# SCH_OpenOllie_2026-02-20.net
KiCad netlist of a schematic drawn in EasyEDA
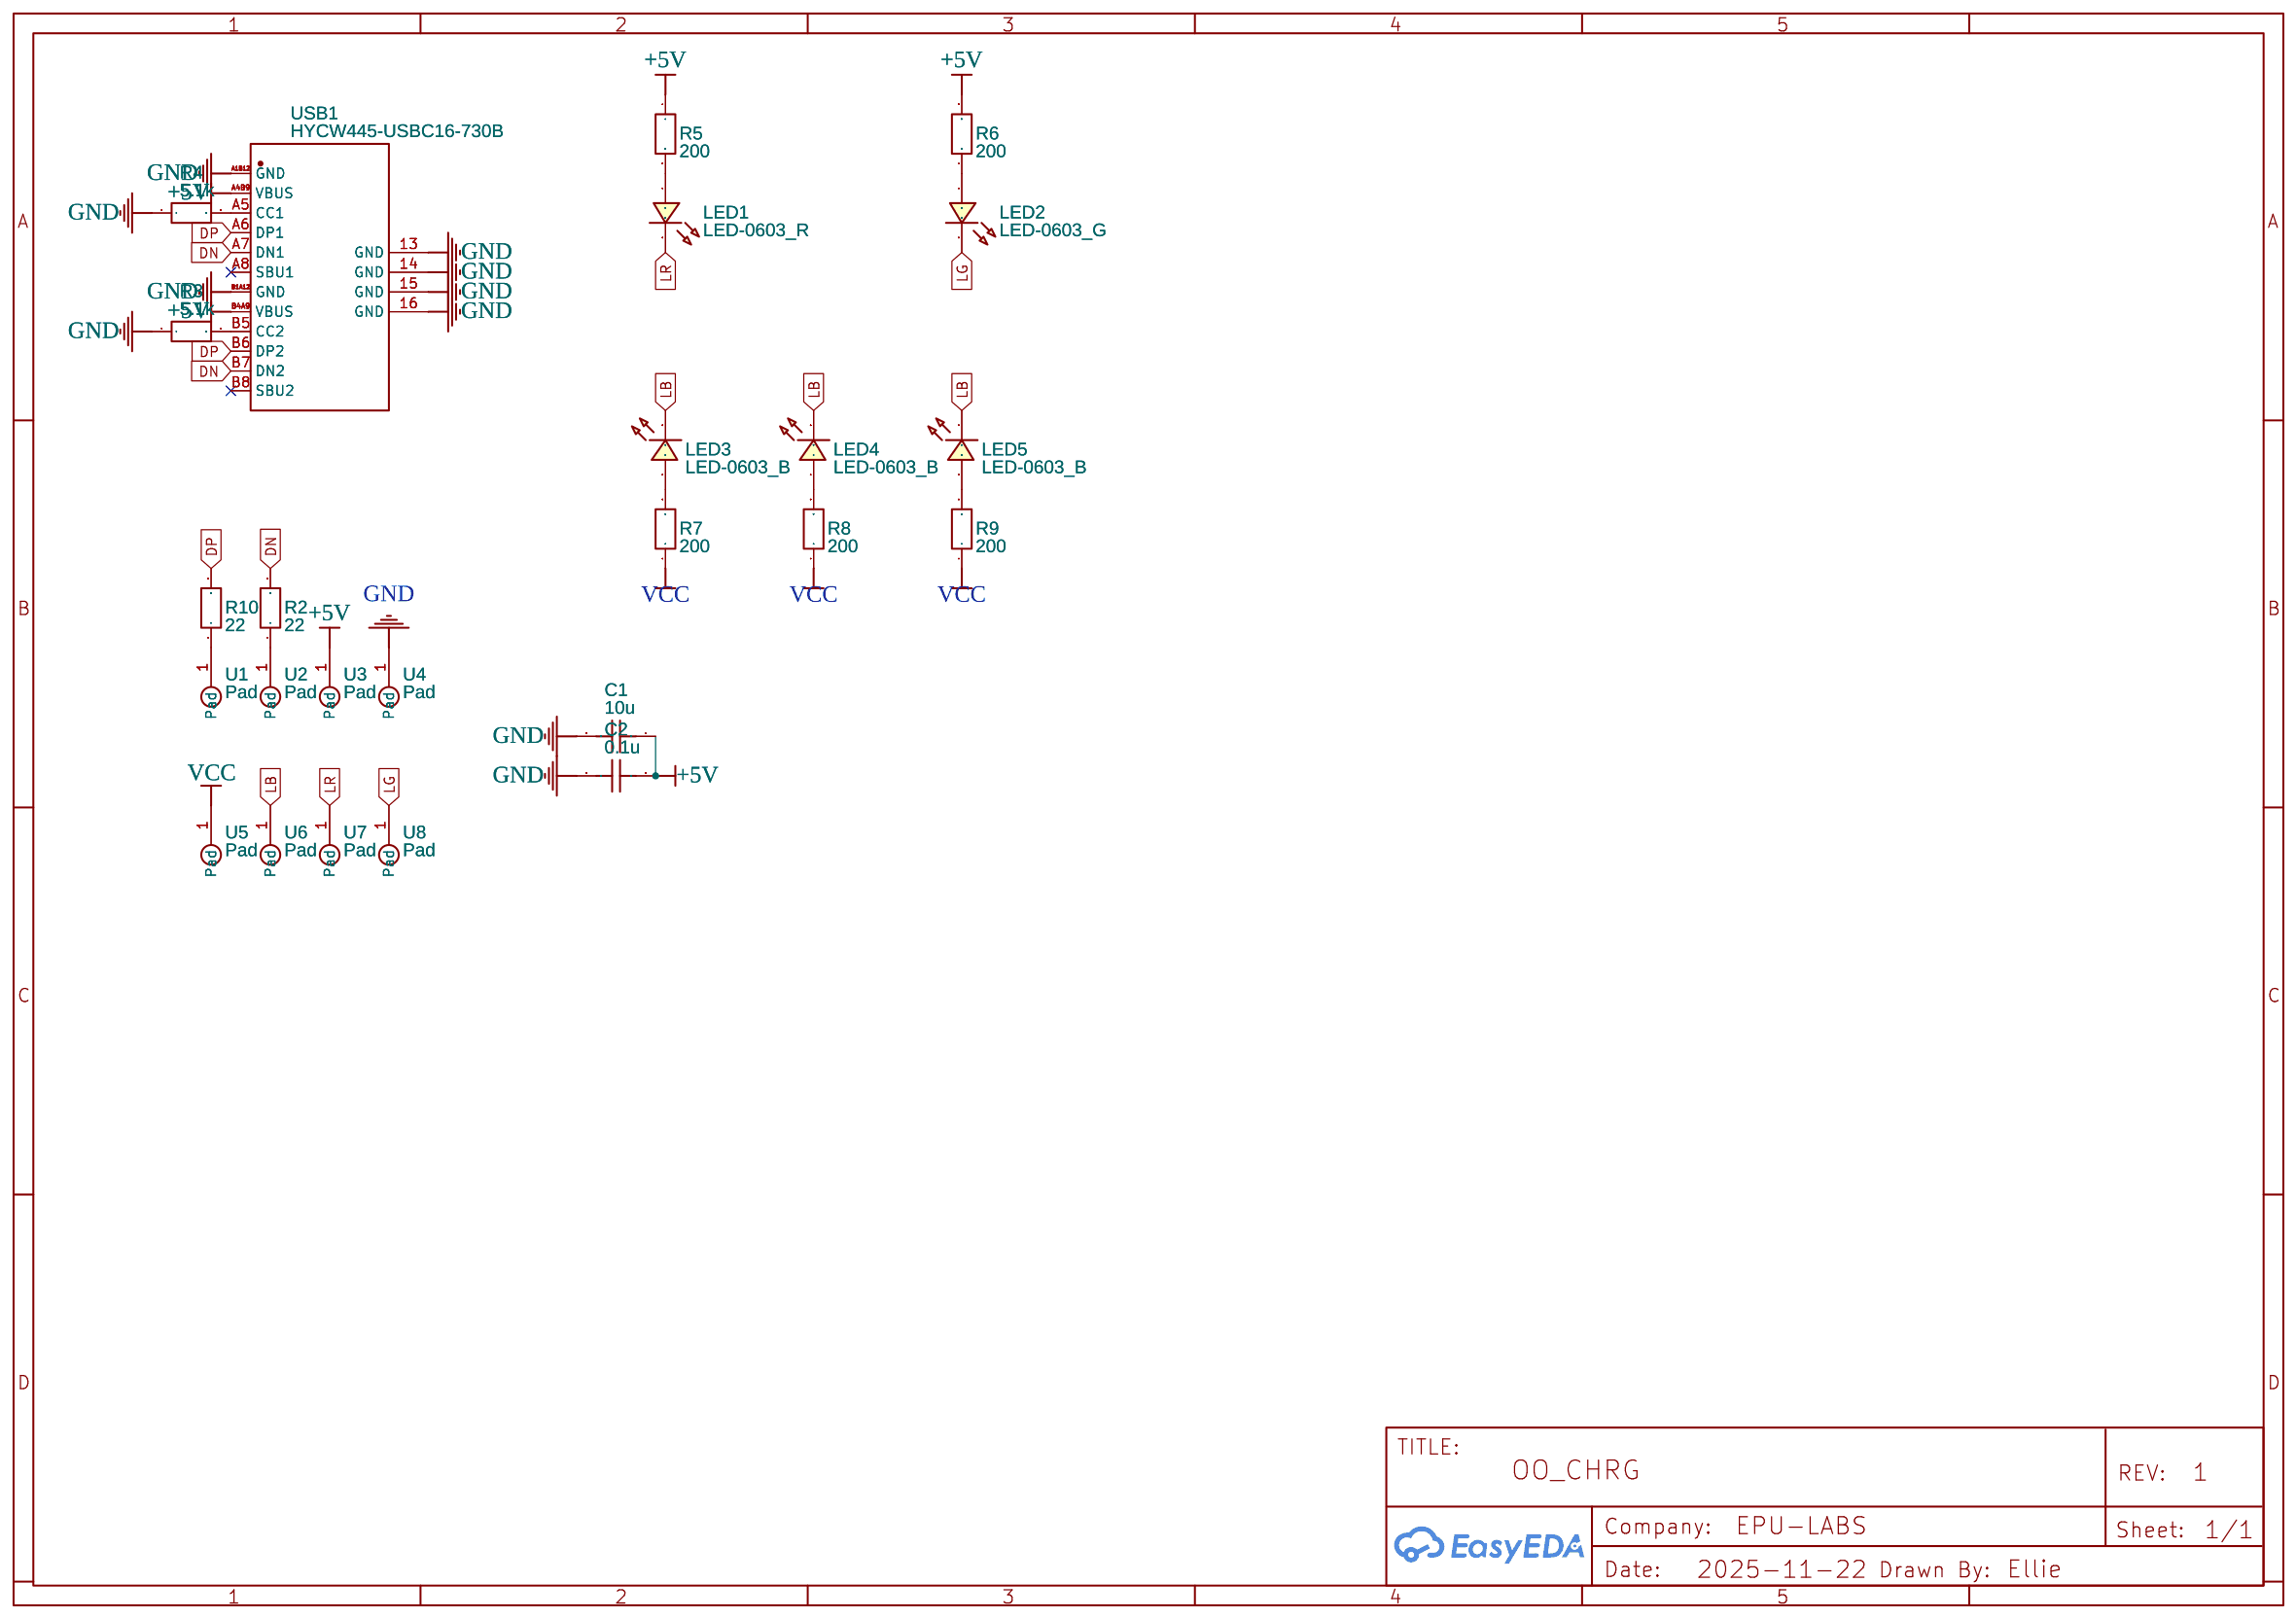
[diagram p0: schematic sheet]

(export (version "E")
  (design (tool "Eeschema 10.0.6"))
  (components
    (comp (ref "C1") (value "10u") (libsource (lib "") (part "C_0805_US")))
    (comp (ref "C2") (value "0.1u") (libsource (lib "") (part "C_0402_US")))
    (comp (ref "LED1")
      (value "LED-0603_R")
      (fields
        (field (name "Manufacturer Part") "19-217/R6C-AL1M2VY/3T")
        (field (name "Manufacturer") "EVERLIGHT(台湾亿光)")
      )
      (libsource (lib "") (part "LED-0603_R"))
    )
    (comp (ref "LED2")
      (value "LED-0603_G")
      (fields
        (field (name "Manufacturer Part") "19-217/GHC-YR1S2/3T")
        (field (name "Manufacturer") "EVERLIGHT(台湾亿光)")
      )
      (libsource (lib "") (part "LED-0603_G"))
    )
    (comp (ref "LED3")
      (value "LED-0603_B")
      (fields
        (field (name "Manufacturer Part") "19-217/BHC-ZL1M2RY/3T")
        (field (name "Manufacturer") "EVERLIGHT(台湾亿光)")
      )
      (libsource (lib "") (part "LED-0603_B"))
    )
    (comp (ref "LED4")
      (value "LED-0603_B")
      (fields
        (field (name "Manufacturer Part") "19-217/BHC-ZL1M2RY/3T")
        (field (name "Manufacturer") "EVERLIGHT(台湾亿光)")
      )
      (libsource (lib "") (part "LED-0603_B"))
    )
    (comp (ref "LED5")
      (value "LED-0603_B")
      (fields
        (field (name "Manufacturer Part") "19-217/BHC-ZL1M2RY/3T")
        (field (name "Manufacturer") "EVERLIGHT(台湾亿光)")
      )
      (libsource (lib "") (part "LED-0603_B"))
    )
    (comp (ref "R2") (value "22") (libsource (lib "") (part "R_0603_EU")))
    (comp (ref "R3") (value "5.1k") (libsource (lib "") (part "R_0603_EU_1")))
    (comp (ref "R4") (value "5.1k") (libsource (lib "") (part "R_0603_EU_1")))
    (comp (ref "R5") (value "200") (libsource (lib "") (part "R_0603_EU_2")))
    (comp (ref "R6") (value "200") (libsource (lib "") (part "R_0603_EU")))
    (comp (ref "R7") (value "200") (libsource (lib "") (part "R_0603_EU")))
    (comp (ref "R8") (value "200") (libsource (lib "") (part "R_0603_EU")))
    (comp (ref "R9") (value "200") (libsource (lib "") (part "R_0603_EU")))
    (comp (ref "R10") (value "22") (libsource (lib "") (part "R_0603_EU")))
    (comp (ref "U1") (value "Pad") (libsource (lib "") (part "Pad")))
    (comp (ref "U2") (value "Pad") (libsource (lib "") (part "Pad")))
    (comp (ref "U3") (value "Pad") (libsource (lib "") (part "Pad")))
    (comp (ref "U4") (value "Pad") (libsource (lib "") (part "Pad")))
    (comp (ref "U5") (value "Pad") (libsource (lib "") (part "Pad")))
    (comp (ref "U6") (value "Pad") (libsource (lib "") (part "Pad")))
    (comp (ref "U7") (value "Pad") (libsource (lib "") (part "Pad")))
    (comp (ref "U8") (value "Pad") (libsource (lib "") (part "Pad")))
    (comp (ref "USB1")
      (value "HYCW445-USBC16-730B")
      (fields (field (name "Manufacturer") "华宇创"))
      (libsource (lib "") (part "HYCW445-USBC16-730B"))
    )
  )
  (nets
    (net (code "1") (name "+5V") (class "Default")
      (node (ref "C1") (pin "1") (pinfunction "1_1") (pintype "unspecified"))
      (node (ref "C2") (pin "2") (pinfunction "2_2") (pintype "unspecified"))
      (node (ref "R5") (pin "1") (pinfunction "1_1") (pintype "unspecified"))
      (node (ref "R6") (pin "2") (pinfunction "2_2") (pintype "unspecified"))
      (node (ref "U3") (pin "1") (pinfunction "Pad_1") (pintype "unspecified"))
      (node (ref "USB1") (pin "A4B9") (pinfunction "VBUS_A4B9") (pintype "unspecified"))
      (node (ref "USB1") (pin "B4A9") (pinfunction "VBUS_B4A9") (pintype "unspecified"))
    )
    (net (code "2") (name "DN") (class "Default")
      (node (ref "R2") (pin "2") (pinfunction "2_2") (pintype "unspecified"))
      (node (ref "USB1") (pin "A7") (pinfunction "DN1_A7") (pintype "unspecified"))
      (node (ref "USB1") (pin "B7") (pinfunction "DN2_B7") (pintype "unspecified"))
    )
    (net (code "3") (name "DP") (class "Default")
      (node (ref "R10") (pin "2") (pinfunction "2_2") (pintype "unspecified"))
      (node (ref "USB1") (pin "A6") (pinfunction "DP1_A6") (pintype "unspecified"))
      (node (ref "USB1") (pin "B6") (pinfunction "DP2_B6") (pintype "unspecified"))
    )
    (net (code "4") (name "GND") (class "Default")
      (node (ref "C1") (pin "2") (pinfunction "2_2") (pintype "unspecified"))
      (node (ref "C2") (pin "1") (pinfunction "1_1") (pintype "unspecified"))
      (node (ref "R3") (pin "1") (pinfunction "1_1") (pintype "unspecified"))
      (node (ref "R4") (pin "1") (pinfunction "1_1") (pintype "unspecified"))
      (node (ref "U4") (pin "1") (pinfunction "Pad_1") (pintype "unspecified"))
      (node (ref "USB1") (pin "13") (pinfunction "GND_13") (pintype "unspecified"))
      (node (ref "USB1") (pin "14") (pinfunction "GND_14") (pintype "unspecified"))
      (node (ref "USB1") (pin "15") (pinfunction "GND_15") (pintype "unspecified"))
      (node (ref "USB1") (pin "16") (pinfunction "GND_16") (pintype "unspecified"))
      (node (ref "USB1") (pin "A1B12") (pinfunction "GND_A1B12") (pintype "unspecified"))
      (node (ref "USB1") (pin "B1A12") (pinfunction "GND_B1A12") (pintype "unspecified"))
    )
    (net (code "5") (name "LB") (class "Default")
      (node (ref "LED3") (pin "2") (pinfunction "2_2") (pintype "unspecified"))
      (node (ref "LED4") (pin "2") (pinfunction "2_2") (pintype "unspecified"))
      (node (ref "LED5") (pin "2") (pinfunction "2_2") (pintype "unspecified"))
      (node (ref "U6") (pin "1") (pinfunction "Pad_1") (pintype "unspecified"))
    )
    (net (code "6") (name "LG") (class "Default")
      (node (ref "LED2") (pin "2") (pinfunction "2_2") (pintype "unspecified"))
      (node (ref "U8") (pin "1") (pinfunction "Pad_1") (pintype "unspecified"))
    )
    (net (code "7") (name "LR") (class "Default")
      (node (ref "LED1") (pin "2") (pinfunction "2_2") (pintype "unspecified"))
      (node (ref "U7") (pin "1") (pinfunction "Pad_1") (pintype "unspecified"))
    )
    (net (code "8") (name "Net-(LED1-Pad1)") (class "Default")
      (node (ref "LED1") (pin "1") (pinfunction "1_1") (pintype "unspecified"))
      (node (ref "R5") (pin "2") (pinfunction "2_2") (pintype "unspecified"))
    )
    (net (code "9") (name "Net-(LED2-Pad1)") (class "Default")
      (node (ref "LED2") (pin "1") (pinfunction "1_1") (pintype "unspecified"))
      (node (ref "R6") (pin "1") (pinfunction "1_1") (pintype "unspecified"))
    )
    (net (code "10") (name "Net-(LED3-Pad1)") (class "Default")
      (node (ref "LED3") (pin "1") (pinfunction "1_1") (pintype "unspecified"))
      (node (ref "R7") (pin "2") (pinfunction "2_2") (pintype "unspecified"))
    )
    (net (code "11") (name "Net-(LED4-Pad1)") (class "Default")
      (node (ref "LED4") (pin "1") (pinfunction "1_1") (pintype "unspecified"))
      (node (ref "R8") (pin "2") (pinfunction "2_2") (pintype "unspecified"))
    )
    (net (code "12") (name "Net-(LED5-Pad1)") (class "Default")
      (node (ref "LED5") (pin "1") (pinfunction "1_1") (pintype "unspecified"))
      (node (ref "R9") (pin "2") (pinfunction "2_2") (pintype "unspecified"))
    )
    (net (code "13") (name "Net-(R2-Pad1)") (class "Default")
      (node (ref "R2") (pin "1") (pinfunction "1_1") (pintype "unspecified"))
      (node (ref "U2") (pin "1") (pinfunction "Pad_1") (pintype "unspecified"))
    )
    (net (code "14") (name "Net-(R10-Pad1)") (class "Default")
      (node (ref "R10") (pin "1") (pinfunction "1_1") (pintype "unspecified"))
      (node (ref "U1") (pin "1") (pinfunction "Pad_1") (pintype "unspecified"))
    )
    (net (code "15") (name "Net-(USB1-CC1)") (class "Default")
      (node (ref "R4") (pin "2") (pinfunction "2_2") (pintype "unspecified"))
      (node (ref "USB1") (pin "A5") (pinfunction "CC1_A5") (pintype "unspecified"))
    )
    (net (code "16") (name "Net-(USB1-CC2)") (class "Default")
      (node (ref "R3") (pin "2") (pinfunction "2_2") (pintype "unspecified"))
      (node (ref "USB1") (pin "B5") (pinfunction "CC2_B5") (pintype "unspecified"))
    )
    (net (code "17") (name "VCC") (class "Default")
      (node (ref "R7") (pin "1") (pinfunction "1_1") (pintype "unspecified"))
      (node (ref "R8") (pin "1") (pinfunction "1_1") (pintype "unspecified"))
      (node (ref "R9") (pin "1") (pinfunction "1_1") (pintype "unspecified"))
      (node (ref "U5") (pin "1") (pinfunction "Pad_1") (pintype "unspecified"))
    )
    (net (code "18") (name "unconnected-(USB1-SBU1-PadA8)") (class "Default")
      (node (ref "USB1") (pin "A8") (pinfunction "SBU1_A8") (pintype "unspecified+no_connect"))
    )
    (net (code "19") (name "unconnected-(USB1-SBU2-PadB8)") (class "Default")
      (node (ref "USB1") (pin "B8") (pinfunction "SBU2_B8") (pintype "unspecified+no_connect"))
    )
  )
)
